# PSU.net
KiCad netlist of a schematic drawn in Altium Designer
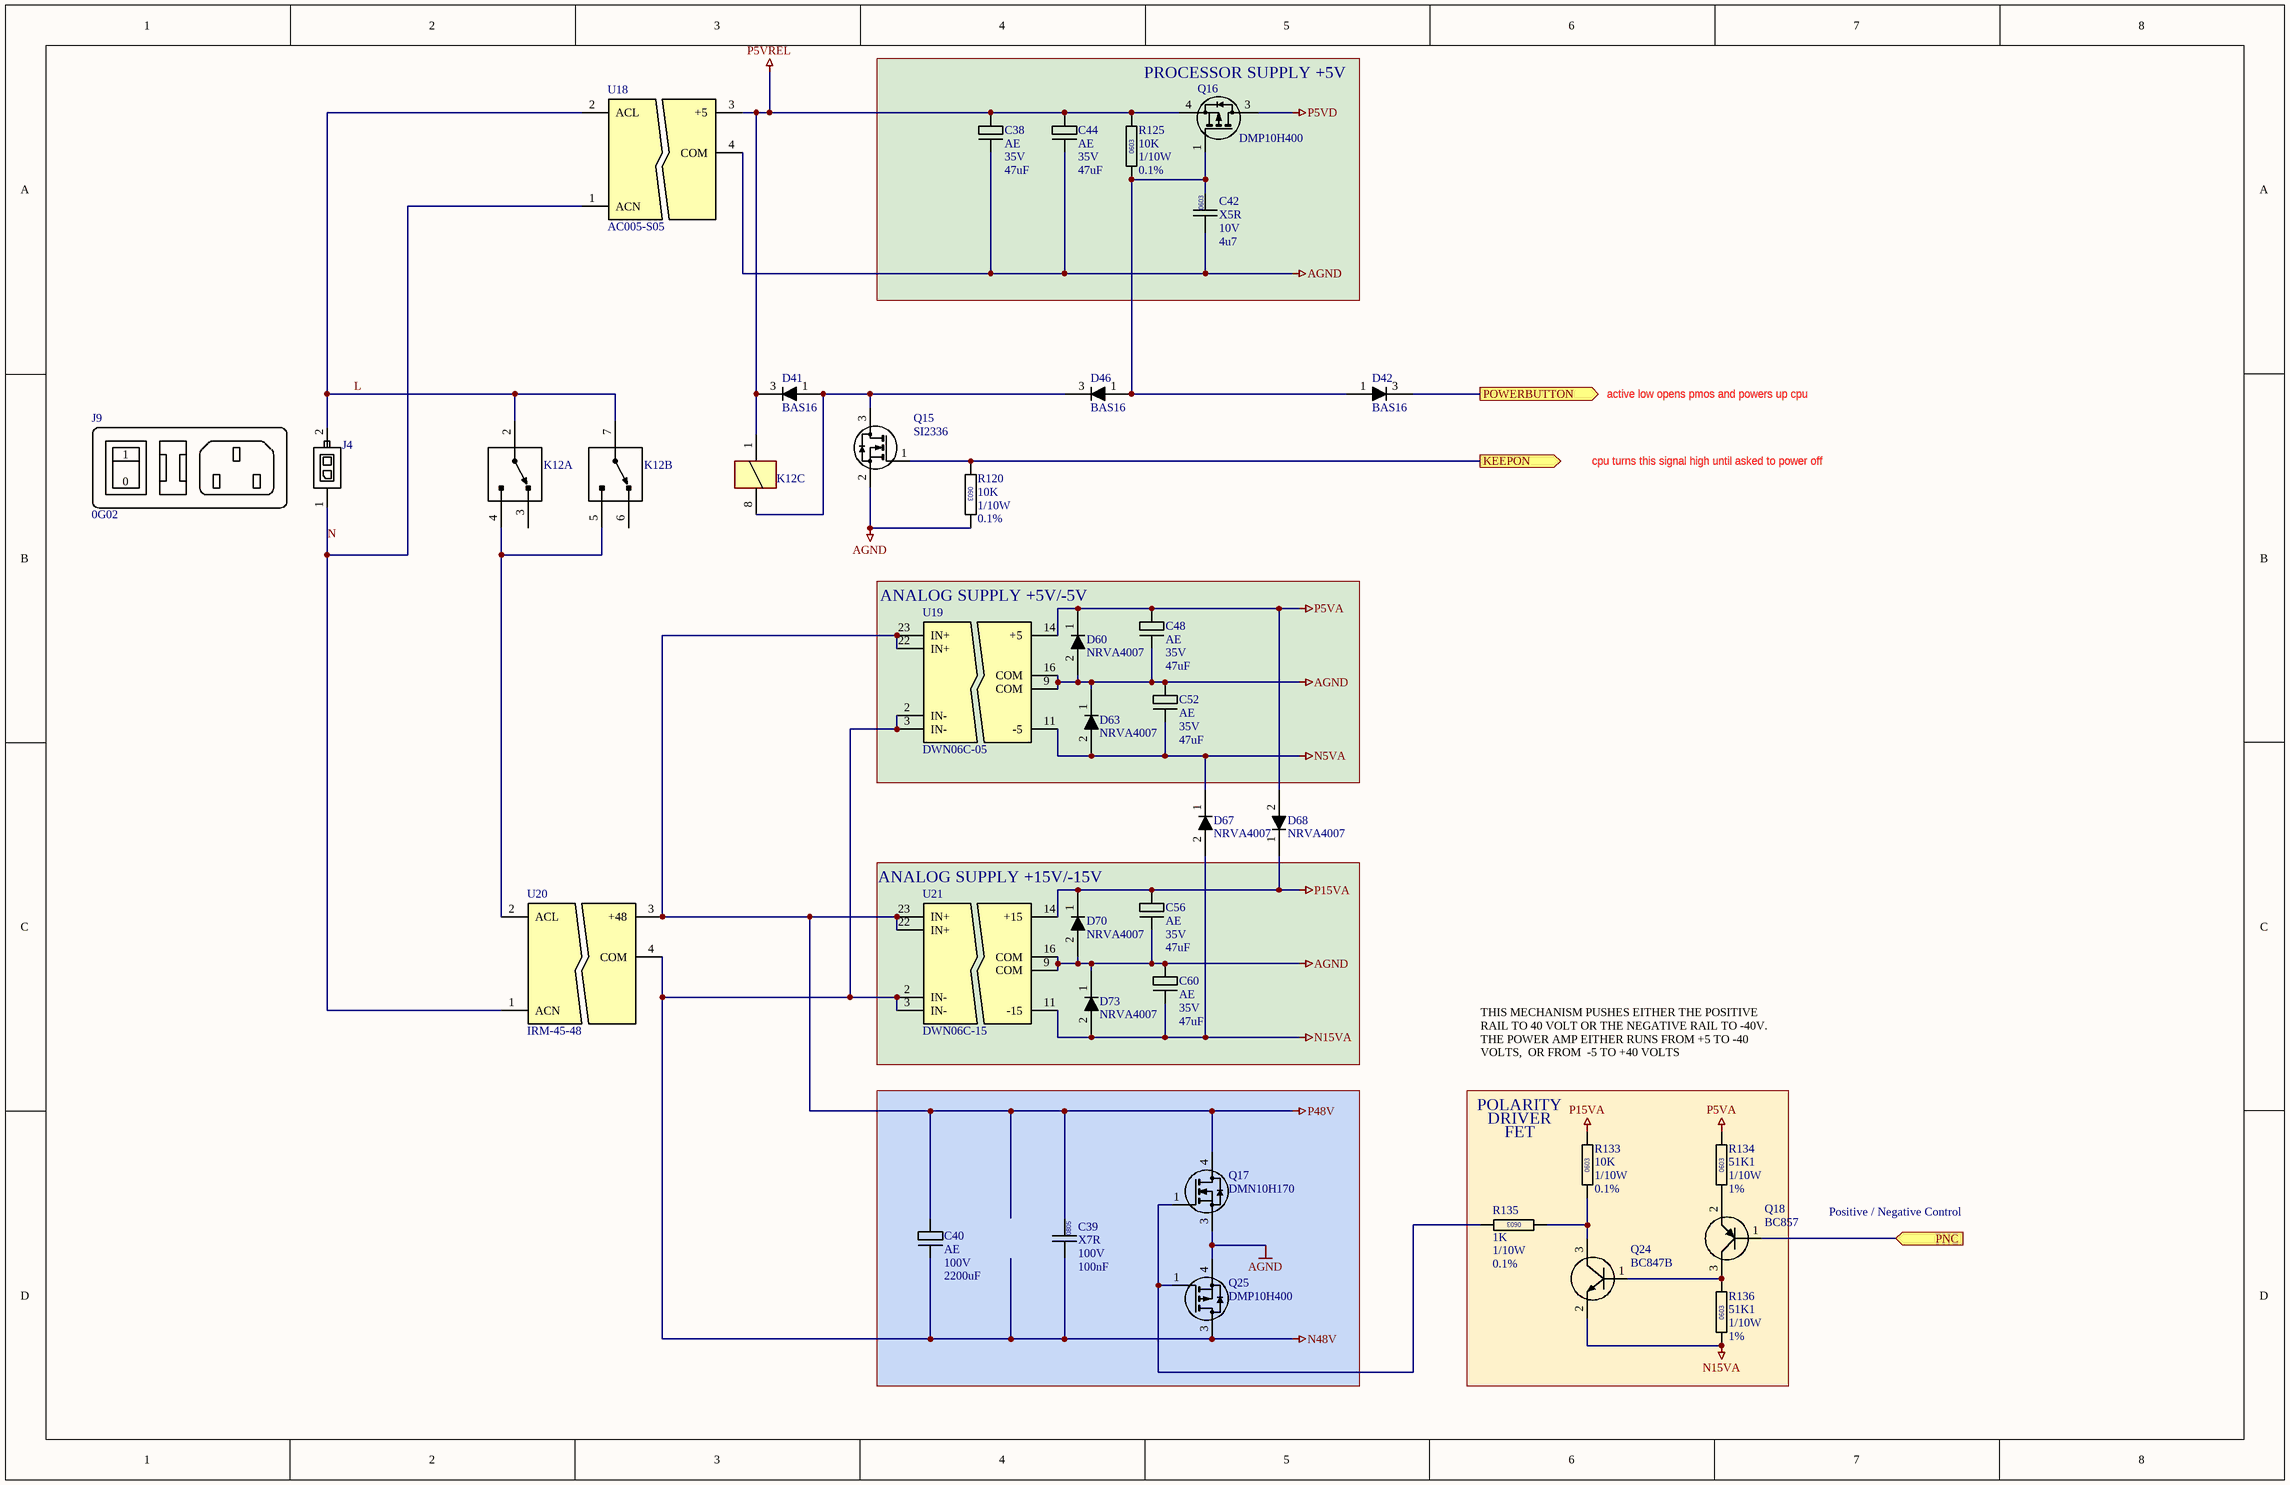
[diagram p0: PSU.SchDoc]

(export (version "E")
  (design (tool "Eeschema 10.0.6"))
  (components
    (comp (ref "C38")
      (value "CAP0603")
      (footprint "CAPAE-KEMET-ESW476M035AE3AA")
      (description "CAPACITOR,ALU,47uF,35V,TH,P0.25mm,D6.3mm,H12.5mm")
      (fields
        (field (name "DIELECTRIC") "AE")
        (field (name "VOLTAGE") "35V")
        (field (name "CAPACITANCE") "47uF")
      )
      (libsource (lib "CAPACITORS") (part "CAPP-AE-47uF-35V-TH025P063D125H"))
    )
    (comp (ref "C39")
      (value "CAP0805")
      (footprint "CAPC0805")
      (description "CAPACITOR,CERAMIC,100nF,100V,X7R,0805")
      (fields
        (field (name "DIELECTRIC") "X7R")
        (field (name "VOLTAGE") "100V")
        (field (name "CAPACITANCE") "100nF")
      )
      (libsource (lib "CAPACITORS") (part "CAPC-0805-100nF-100V"))
    )
    (comp (ref "C40")
      (value "CAP0603")
      (footprint "CAPAE-NICHICON-LGY2A222MELC30")
      (description "CAPACITOR,ALU,2200uF,100V,TH,P10mm,D35mm,H32mm,SNAP")
      (fields
        (field (name "DIELECTRIC") "AE")
        (field (name "VOLTAGE") "100V")
        (field (name "CAPACITANCE") "2200uF")
      )
      (libsource (lib "CAPACITORS") (part "CAPP-AE-2200uF-100V-TH100P350D320H"))
    )
    (comp (ref "C42")
      (value "CAP0603")
      (footprint "CAPC0603")
      (description "CAPACITOR,CERAMIC,4u7,10V,X5R,0603")
      (fields
        (field (name "DIELECTRIC") "X5R")
        (field (name "VOLTAGE") "10V")
        (field (name "CAPACITANCE") "4u7")
      )
      (libsource (lib "CAPACITORS") (part "CAPC-0603-4u7-10V-X5R"))
    )
    (comp (ref "C44")
      (value "CAP0603")
      (footprint "CAPAE-KEMET-ESW476M035AE3AA")
      (description "CAPACITOR,ALU,47uF,35V,TH,P0.25mm,D6.3mm,H12.5mm")
      (fields
        (field (name "DIELECTRIC") "AE")
        (field (name "VOLTAGE") "35V")
        (field (name "CAPACITANCE") "47uF")
      )
      (libsource (lib "CAPACITORS") (part "CAPP-AE-47uF-35V-TH025P063D125H"))
    )
    (comp (ref "C48")
      (value "CAP0603")
      (footprint "CAPAE-KEMET-ESW476M035AE3AA")
      (description "CAPACITOR,ALU,47uF,35V,TH,P0.25mm,D6.3mm,H12.5mm")
      (fields
        (field (name "DIELECTRIC") "AE")
        (field (name "VOLTAGE") "35V")
        (field (name "CAPACITANCE") "47uF")
      )
      (libsource (lib "CAPACITORS") (part "CAPP-AE-47uF-35V-TH025P063D125H"))
    )
    (comp (ref "C52")
      (value "CAP0603")
      (footprint "CAPAE-KEMET-ESW476M035AE3AA")
      (description "CAPACITOR,ALU,47uF,35V,TH,P0.25mm,D6.3mm,H12.5mm")
      (fields
        (field (name "DIELECTRIC") "AE")
        (field (name "VOLTAGE") "35V")
        (field (name "CAPACITANCE") "47uF")
      )
      (libsource (lib "CAPACITORS") (part "CAPP-AE-47uF-35V-TH025P063D125H"))
    )
    (comp (ref "C56")
      (value "CAP0603")
      (footprint "CAPAE-KEMET-ESW476M035AE3AA")
      (description "CAPACITOR,ALU,47uF,35V,TH,P0.25mm,D6.3mm,H12.5mm")
      (fields
        (field (name "DIELECTRIC") "AE")
        (field (name "VOLTAGE") "35V")
        (field (name "CAPACITANCE") "47uF")
      )
      (libsource (lib "CAPACITORS") (part "CAPP-AE-47uF-35V-TH025P063D125H"))
    )
    (comp (ref "C60")
      (value "CAP0603")
      (footprint "CAPAE-KEMET-ESW476M035AE3AA")
      (description "CAPACITOR,ALU,47uF,35V,TH,P0.25mm,D6.3mm,H12.5mm")
      (fields
        (field (name "DIELECTRIC") "AE")
        (field (name "VOLTAGE") "35V")
        (field (name "CAPACITANCE") "47uF")
      )
      (libsource (lib "CAPACITORS") (part "CAPP-AE-47uF-35V-TH025P063D125H"))
    )
    (comp (ref "D41")
      (value "BAS16")
      (footprint "SOT23")
      (description "DIODE,RECTIFIER,75V,0.3A,BAS16,SOT23")
      (libsource (lib "DIODES") (part "DIODE-RECTIFIER-DIODES-BAS16-SOT23"))
    )
    (comp (ref "D42")
      (value "BAS16")
      (footprint "SOT23")
      (description "DIODE,RECTIFIER,75V,0.3A,BAS16,SOT23")
      (libsource (lib "DIODES") (part "DIODE-RECTIFIER-DIODES-BAS16-SOT23"))
    )
    (comp (ref "D46")
      (value "BAS16")
      (footprint "SOT23")
      (description "DIODE,RECTIFIER,75V,0.3A,BAS16,SOT23")
      (libsource (lib "DIODES") (part "DIODE-RECTIFIER-DIODES-BAS16-SOT23"))
    )
    (comp (ref "D60")
      (value "NRVA4007")
      (footprint "DO214AC")
      (description "DIODE,RECTIFIER,1000V,1A,ONSEMI,NRVA4007,SMA")
      (libsource (lib "DIODES") (part "DIODE-ONSEMI-NRVA4007T3G"))
    )
    (comp (ref "D63")
      (value "NRVA4007")
      (footprint "DO214AC")
      (description "DIODE,RECTIFIER,1000V,1A,ONSEMI,NRVA4007,SMA")
      (libsource (lib "DIODES") (part "DIODE-ONSEMI-NRVA4007T3G"))
    )
    (comp (ref "D67")
      (value "NRVA4007")
      (footprint "DO214AC")
      (description "DIODE,RECTIFIER,1000V,1A,ONSEMI,NRVA4007,SMA")
      (libsource (lib "DIODES") (part "DIODE-ONSEMI-NRVA4007T3G"))
    )
    (comp (ref "D68")
      (value "NRVA4007")
      (footprint "DO214AC")
      (description "DIODE,RECTIFIER,1000V,1A,ONSEMI,NRVA4007,SMA")
      (libsource (lib "DIODES") (part "DIODE-ONSEMI-NRVA4007T3G"))
    )
    (comp (ref "D70")
      (value "NRVA4007")
      (footprint "DO214AC")
      (description "DIODE,RECTIFIER,1000V,1A,ONSEMI,NRVA4007,SMA")
      (libsource (lib "DIODES") (part "DIODE-ONSEMI-NRVA4007T3G"))
    )
    (comp (ref "D73")
      (value "NRVA4007")
      (footprint "DO214AC")
      (description "DIODE,RECTIFIER,1000V,1A,ONSEMI,NRVA4007,SMA")
      (libsource (lib "DIODES") (part "DIODE-ONSEMI-NRVA4007T3G"))
    )
    (comp (ref "J4")
      (value "CONNECTOR-MOLEX-43045-0202")
      (footprint "CONN-MOLEX-430450214")
      (description "CONN,1X2,MOLEX, MICROFIT,VERT")
      (libsource (lib "CONNECTORS") (part "CONN-MOLEX-430450214"))
    )
    (comp (ref "J9")
      (value "0G02")
      (description "CONN,POWER,IEC,SWITCH,FUSE ASSEMBLY,PANELMOUNT")
      (libsource (lib "CONNECTORS") (part "CONN-DELTA-0G02"))
    )
    (comp (ref "K12")
      (value "RELAY-CIT-J104B2C5VDC.20S")
      (footprint "RELAY-CIT-J104B2C5VDC.20S")
      (description "RELAY,DPDT,5V COIL,250VAC,3A")
      (libsource (lib "") (part "RELAY-CIT-J104B2C5VDC.20S_1"))
    )
    (comp (ref "Q15")
      (value "SI2336")
      (footprint "SOT23")
      (description "XSTR,NMOS,30V,4.3A,SI2336DS-T1-BE3.SOT23")
      (libsource (lib "TRANSISTORS") (part "XSTR-NMOS-VISHAY-SI2336DS-T1-BE3"))
    )
    (comp (ref "Q16")
      (value "DMP10H400")
      (footprint "DPAK")
      (description "XSTR,PMOS,100V,5.6A,DMP10H400SK3-13,DPAK")
      (libsource (lib "TRANSISTORS") (part "XSTR-PMOS-DIODES-DMP10H400SK3-13"))
    )
    (comp (ref "Q17")
      (value "DMN10H170")
      (footprint "DPAK")
      (description "XSTR,NMOS,100V,12A,DMN10H170SK3-13,DPAK")
      (libsource (lib "TRANSISTORS") (part "XSTR-NMOS-DIODES-DMN10H170SK3-13"))
    )
    (comp (ref "Q18")
      (value "BC857")
      (footprint "SOT23")
      (description "XSTR,PNP,SOT23,BC857,SOT23")
      (libsource (lib "TRANSISTORS") (part "XSTR-PNP-BC857"))
    )
    (comp (ref "Q24")
      (value "BC847B")
      (footprint "SOT23")
      (description "XSTR,NPN,45V,0.1A,,BC847B,SOT23")
      (libsource (lib "TRANSISTORS") (part "XSTR-NPN-BC847"))
    )
    (comp (ref "Q25")
      (value "DMP10H400")
      (footprint "DPAK")
      (description "XSTR,PMOS,100V,5.6A,DMP10H400SK3-13,DPAK")
      (libsource (lib "TRANSISTORS") (part "XSTR-PMOS-DIODES-DMP10H400SK3-13"))
    )
    (comp (ref "R120")
      (value "10K")
      (footprint "RESC0603")
      (description "RESISTOR,10K,0.1%,100mW,0603 (1608)")
      (fields
        (field (name "POWER") "1/10W")
        (field (name "TOLERANCE") "0.1%")
        (field (name "Comment") "RESC0603")
      )
      (libsource (lib "RESISTORS") (part "RESC-0603-10K-0.1%-1/10W"))
    )
    (comp (ref "R125")
      (value "10K")
      (footprint "RESC0603")
      (description "RESISTOR,10K,0.1%,100mW,0603 (1608)")
      (fields
        (field (name "POWER") "1/10W")
        (field (name "TOLERANCE") "0.1%")
        (field (name "Comment") "RESC0603")
      )
      (libsource (lib "RESISTORS") (part "RESC-0603-10K-0.1%-1/10W"))
    )
    (comp (ref "R133")
      (value "10K")
      (footprint "RESC0603")
      (description "RESISTOR,10K,0.1%,100mW,0603 (1608)")
      (fields
        (field (name "POWER") "1/10W")
        (field (name "TOLERANCE") "0.1%")
        (field (name "Comment") "RESC0603")
      )
      (libsource (lib "RESISTORS") (part "RESC-0603-10K-0.1%-1/10W"))
    )
    (comp (ref "R134")
      (value "51K1")
      (footprint "RESC0603")
      (description "RESISTOR,51K1,1%,100mW,0603 (1608)")
      (fields
        (field (name "POWER") "1/10W")
        (field (name "TOLERANCE") "1%")
        (field (name "Comment") "RESC0603")
      )
      (libsource (lib "RESISTORS") (part "RESC-0603-51K1-1%-1/10W"))
    )
    (comp (ref "R135")
      (value "1K")
      (footprint "RESC0603")
      (description "RESISTOR,1K,0.1%,100mW,0603 (1608)")
      (fields
        (field (name "POWER") "1/10W")
        (field (name "TOLERANCE") "0.1%")
        (field (name "Comment") "RESC0603")
      )
      (libsource (lib "RESISTORS") (part "RESC-0603-1K-0.1%-1/10W"))
    )
    (comp (ref "R136")
      (value "51K1")
      (footprint "RESC0603")
      (description "RESISTOR,51K1,1%,100mW,0603 (1608)")
      (fields
        (field (name "POWER") "1/10W")
        (field (name "TOLERANCE") "1%")
        (field (name "Comment") "RESC0603")
      )
      (libsource (lib "RESISTORS") (part "RESC-0603-51K1-1%-1/10W"))
    )
    (comp (ref "U18")
      (value "AC005-S05")
      (footprint "MODULE-ADAMTECH-AC005-S05")
      (description "MOD,AC/DC,ISO,90...264 AC,+5V OUT,1A")
      (libsource (lib "SPECIAL") (part "MODULE-ADAMTECH-AC005-S05"))
    )
    (comp (ref "U19")
      (value "DWN06C-05")
      (footprint "MODULE-MEANWELL-DCWN06C")
      (description "MOD,DC/DC,ISO,DC 36...72V IN,+/-5V OUT,1A")
      (libsource (lib "SPECIAL") (part "MODULE-MEANWELL-DWN06C-05"))
    )
    (comp (ref "U20")
      (value "IRM-45-48")
      (footprint "MODULE-MEANWELL-IRM-45-48")
      (description "MOD,AC/DC,ISO,90...264 AC,+48V OUT,1A")
      (libsource (lib "SPECIAL") (part "MODULE-MEANWELL-IRM-45-48"))
    )
    (comp (ref "U21")
      (value "DWN06C-15")
      (footprint "MODULE-MEANWELL-DCWN06C")
      (description "MOD,DC/DC,ISO,DC 36...72V IN,+/-15V OUT,200mA")
      (libsource (lib "SPECIAL") (part "MODULE-MEANWELL-DWN06C-15"))
    )
  )
  (nets
    (net (code "1") (name "/KEEPON") (class "Default")
      (node (ref "Q15") (pin "1") (pinfunction "G1_1") (pintype "passive"))
      (node (ref "R120") (pin "2") (pintype "passive"))
    )
    (net (code "2") (name "/L") (class "Default")
      (node (ref "J4") (pin "2") (pinfunction "2_2") (pintype "passive"))
      (node (ref "K12") (pin "2") (pinfunction "NC_2") (pintype "passive"))
      (node (ref "K12") (pin "7") (pinfunction "NC_7") (pintype "passive"))
      (node (ref "U18") (pin "2") (pinfunction "ACL_2") (pintype "passive"))
    )
    (net (code "3") (name "/N") (class "Default")
      (node (ref "J4") (pin "1") (pinfunction "1_1") (pintype "passive"))
      (node (ref "U18") (pin "1") (pinfunction "ACN_1") (pintype "passive"))
      (node (ref "U20") (pin "1") (pinfunction "ACN_1") (pintype "passive"))
    )
    (net (code "4") (name "/PNC") (class "Default")
      (node (ref "Q18") (pin "1") (pinfunction "B_1") (pintype "passive"))
    )
    (net (code "5") (name "/POWERBUTTON") (class "Default")
      (node (ref "D42") (pin "3") (pinfunction "K_3") (pintype "passive"))
    )
    (net (code "6") (name "AGND") (class "Default")
      (node (ref "C38") (pin "2") (pintype "passive"))
      (node (ref "C42") (pin "2") (pintype "passive"))
      (node (ref "C44") (pin "2") (pintype "passive"))
      (node (ref "C48") (pin "2") (pintype "passive"))
      (node (ref "C52") (pin "1") (pintype "passive"))
      (node (ref "C56") (pin "2") (pintype "passive"))
      (node (ref "C60") (pin "1") (pintype "passive"))
      (node (ref "D60") (pin "2") (pinfunction "A_2") (pintype "passive"))
      (node (ref "D63") (pin "1") (pinfunction "K_1") (pintype "passive"))
      (node (ref "D70") (pin "2") (pinfunction "A_2") (pintype "passive"))
      (node (ref "D73") (pin "1") (pinfunction "K_1") (pintype "passive"))
      (node (ref "Q15") (pin "2") (pinfunction "S_2") (pintype "passive"))
      (node (ref "Q17") (pin "3") (pinfunction "S_3") (pintype "passive"))
      (node (ref "Q25") (pin "4") (pinfunction "S_4") (pintype "passive"))
      (node (ref "R120") (pin "1") (pintype "passive"))
      (node (ref "U18") (pin "4") (pinfunction "COM_4") (pintype "passive"))
      (node (ref "U19") (pin "16") (pinfunction "COM_16") (pintype "passive"))
      (node (ref "U19") (pin "9") (pinfunction "COM_9") (pintype "passive"))
      (node (ref "U21") (pin "16") (pinfunction "COM_16") (pintype "passive"))
      (node (ref "U21") (pin "9") (pinfunction "COM_9") (pintype "passive"))
    )
    (net (code "7") (name "N5VA") (class "Default")
      (node (ref "C52") (pin "2") (pintype "passive"))
      (node (ref "D63") (pin "2") (pinfunction "A_2") (pintype "passive"))
      (node (ref "D67") (pin "1") (pinfunction "K_1") (pintype "passive"))
      (node (ref "U19") (pin "11") (pinfunction "-5_11") (pintype "passive"))
    )
    (net (code "8") (name "N15VA") (class "Default")
      (node (ref "C60") (pin "2") (pintype "passive"))
      (node (ref "D67") (pin "2") (pinfunction "A_2") (pintype "passive"))
      (node (ref "D73") (pin "2") (pinfunction "A_2") (pintype "passive"))
      (node (ref "Q24") (pin "2") (pinfunction "E_2") (pintype "passive"))
      (node (ref "R136") (pin "2") (pintype "passive"))
      (node (ref "U21") (pin "11") (pinfunction "-15_11") (pintype "passive"))
    )
    (net (code "9") (name "N48V") (class "Default")
      (node (ref "C39") (pin "2") (pintype "passive"))
      (node (ref "C40") (pin "2") (pintype "passive"))
      (node (ref "Q25") (pin "3") (pinfunction "D_3") (pintype "passive"))
      (node (ref "U19") (pin "2") (pinfunction "IN-_2") (pintype "passive"))
      (node (ref "U19") (pin "3") (pinfunction "IN-_3") (pintype "passive"))
      (node (ref "U20") (pin "4") (pinfunction "COM_4") (pintype "passive"))
      (node (ref "U21") (pin "2") (pinfunction "IN-_2") (pintype "passive"))
      (node (ref "U21") (pin "3") (pinfunction "IN-_3") (pintype "passive"))
    )
    (net (code "10") (name "Net-(D41-A)") (class "Default")
      (node (ref "D41") (pin "1") (pinfunction "A_1") (pintype "passive"))
      (node (ref "D46") (pin "3") (pinfunction "K_3") (pintype "passive"))
      (node (ref "K12") (pin "8") (pinfunction "8_8") (pintype "passive"))
      (node (ref "Q15") (pin "3") (pinfunction "D_3") (pintype "passive"))
    )
    (net (code "11") (name "Net-(D42-A)") (class "Default")
      (node (ref "C42") (pin "1") (pintype "passive"))
      (node (ref "D42") (pin "1") (pinfunction "A_1") (pintype "passive"))
      (node (ref "D46") (pin "1") (pinfunction "A_1") (pintype "passive"))
      (node (ref "Q16") (pin "1") (pinfunction "G1_1") (pintype "passive"))
      (node (ref "R125") (pin "2") (pintype "passive"))
    )
    (net (code "12") (name "Net-(K12A-NO)") (class "Default")
      (node (ref "K12") (pin "4") (pinfunction "NO_4") (pintype "passive"))
      (node (ref "K12") (pin "5") (pinfunction "NO_5") (pintype "passive"))
      (node (ref "U20") (pin "2") (pinfunction "ACL_2") (pintype "passive"))
    )
    (net (code "13") (name "Net-(Q17-G1)") (class "Default")
      (node (ref "Q17") (pin "1") (pinfunction "G1_1") (pintype "passive"))
      (node (ref "Q25") (pin "1") (pinfunction "G1_1") (pintype "passive"))
      (node (ref "R135") (pin "2") (pintype "passive"))
    )
    (net (code "14") (name "Net-(Q18-C)") (class "Default")
      (node (ref "Q18") (pin "3") (pinfunction "C_3") (pintype "passive"))
      (node (ref "Q24") (pin "1") (pinfunction "B_1") (pintype "passive"))
      (node (ref "R136") (pin "1") (pintype "passive"))
    )
    (net (code "15") (name "Net-(Q18-E)") (class "Default")
      (node (ref "Q18") (pin "2") (pinfunction "E_2") (pintype "passive"))
      (node (ref "R134") (pin "2") (pintype "passive"))
    )
    (net (code "16") (name "Net-(Q24-C)") (class "Default")
      (node (ref "Q24") (pin "3") (pinfunction "C_3") (pintype "passive"))
      (node (ref "R133") (pin "2") (pintype "passive"))
      (node (ref "R135") (pin "1") (pintype "passive"))
    )
    (net (code "17") (name "P5VA") (class "Default")
      (node (ref "C48") (pin "1") (pintype "passive"))
      (node (ref "D60") (pin "1") (pinfunction "K_1") (pintype "passive"))
      (node (ref "D68") (pin "2") (pinfunction "A_2") (pintype "passive"))
      (node (ref "R134") (pin "1") (pintype "passive"))
      (node (ref "U19") (pin "14") (pinfunction "+5_14") (pintype "passive"))
    )
    (net (code "18") (name "P5VD") (class "Default")
      (node (ref "Q16") (pin "3") (pinfunction "D_3") (pintype "passive"))
    )
    (net (code "19") (name "P5VREL") (class "Default")
      (node (ref "C38") (pin "1") (pintype "passive"))
      (node (ref "C44") (pin "1") (pintype "passive"))
      (node (ref "D41") (pin "3") (pinfunction "K_3") (pintype "passive"))
      (node (ref "K12") (pin "1") (pinfunction "1_1") (pintype "passive"))
      (node (ref "Q16") (pin "4") (pinfunction "S_4") (pintype "passive"))
      (node (ref "R125") (pin "1") (pintype "passive"))
      (node (ref "U18") (pin "3") (pinfunction "+5_3") (pintype "passive"))
    )
    (net (code "20") (name "P15VA") (class "Default")
      (node (ref "C56") (pin "1") (pintype "passive"))
      (node (ref "D68") (pin "1") (pinfunction "K_1") (pintype "passive"))
      (node (ref "D70") (pin "1") (pinfunction "K_1") (pintype "passive"))
      (node (ref "R133") (pin "1") (pintype "passive"))
      (node (ref "U21") (pin "14") (pinfunction "+15_14") (pintype "passive"))
    )
    (net (code "21") (name "P48V") (class "Default")
      (node (ref "C39") (pin "1") (pintype "passive"))
      (node (ref "C40") (pin "1") (pintype "passive"))
      (node (ref "Q17") (pin "4") (pinfunction "D_4") (pintype "passive"))
      (node (ref "U19") (pin "22") (pinfunction "IN+_22") (pintype "passive"))
      (node (ref "U19") (pin "23") (pinfunction "IN+_23") (pintype "passive"))
      (node (ref "U20") (pin "3") (pinfunction "+48_3") (pintype "passive"))
      (node (ref "U21") (pin "22") (pinfunction "IN+_22") (pintype "passive"))
      (node (ref "U21") (pin "23") (pinfunction "IN+_23") (pintype "passive"))
    )
    (net (code "22") (name "unconnected-(K12A-COM-Pad3)") (class "Default")
      (node (ref "K12") (pin "3") (pinfunction "COM_3") (pintype "passive"))
    )
    (net (code "23") (name "unconnected-(K12B-COM-Pad6)") (class "Default")
      (node (ref "K12") (pin "6") (pinfunction "COM_6") (pintype "passive"))
    )
  )
)
